# speaker-board.net
KiCad netlist of a schematic drawn in EAGLE
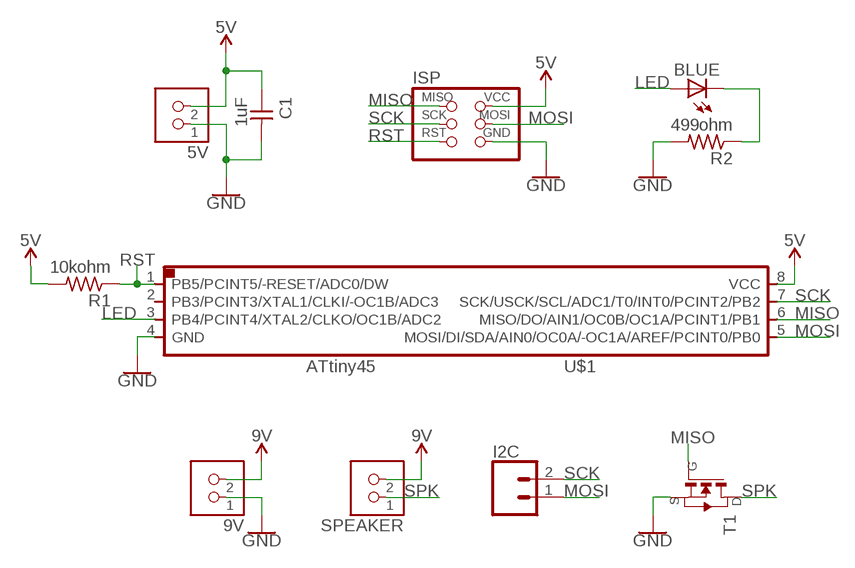
[diagram p0: schematic, sheet 1]

(export (version "E")
  (design (tool "Eeschema 10.0.6"))
  (components
    (comp (ref "5V")
      (value "TERM-1X02-FABLAB")
      (footprint "eagle-import:ED555DS-2DS")
      (libsource (lib "eagle-import") (part "TERM-1X02-FABLAB"))
    )
    (comp (ref "9V")
      (value "TERM-1X02-FABLAB")
      (footprint "eagle-import:ED555DS-2DS")
      (libsource (lib "eagle-import") (part "TERM-1X02-FABLAB"))
    )
    (comp (ref "BLUE")
      (value "LEDFAB1206")
      (footprint "eagle-import:LED1206FAB")
      (libsource (lib "eagle-import") (part "LEDFAB1206"))
    )
    (comp (ref "C1")
      (value "1uF")
      (footprint "eagle-import:C1206FAB")
      (libsource (lib "eagle-import") (part "CAP-UNPOLARIZEDFAB"))
    )
    (comp (ref "I2C")
      (value "CONN_021X02_NO_SILK")
      (footprint "eagle-import:1X02_NO_SILK")
      (libsource (lib "eagle-import") (part "CONN_021X02_NO_SILK"))
    )
    (comp (ref "ISP")
      (value "AVRISPSMD")
      (footprint "eagle-import:2X03SMD")
      (libsource (lib "eagle-import") (part "AVRISPSMD"))
    )
    (comp (ref "R1")
      (value "10kohm")
      (footprint "eagle-import:R1206FAB")
      (libsource (lib "eagle-import") (part "RES-US1206FAB"))
    )
    (comp (ref "R2")
      (value "499ohm")
      (footprint "eagle-import:R1206FAB")
      (libsource (lib "eagle-import") (part "RES-US1206FAB"))
    )
    (comp (ref "SPEAKER")
      (value "TERM-1X02-FABLAB")
      (footprint "eagle-import:ED555DS-2DS")
      (libsource (lib "eagle-import") (part "TERM-1X02-FABLAB"))
    )
    (comp (ref "T1")
      (value "NMOSFETSOT23")
      (footprint "eagle-import:SOT-23")
      (libsource (lib "eagle-import") (part "NMOSFETSOT23"))
    )
    (comp (ref "U$1")
      (value "ATTINY45SI")
      (footprint "eagle-import:SOIC8")
      (libsource (lib "eagle-import") (part "ATTINY45SI"))
    )
  )
  (nets
    (net (code "1") (name "/LED") (class "Default")
      (node (ref "BLUE") (pin "1") (pinfunction "A_1") (pintype "passive"))
      (node (ref "U$1") (pin "3") (pinfunction "PB4/PCINT4/XTAL2/CLKO/OC1B/ADC2_3") (pintype "bidirectional"))
    )
    (net (code "2") (name "/MISO") (class "Default")
      (node (ref "ISP") (pin "1") (pinfunction "MISO_1") (pintype "passive"))
      (node (ref "T1") (pin "3") (pinfunction "G_3") (pintype "passive"))
      (node (ref "U$1") (pin "6") (pinfunction "MISO/DO/AIN1/OC0B/OC1A/PCINT1/PB1_6") (pintype "bidirectional"))
    )
    (net (code "3") (name "/MOSI") (class "Default")
      (node (ref "I2C") (pin "1") (pinfunction "1_1") (pintype "passive"))
      (node (ref "ISP") (pin "4") (pinfunction "MOSI_4") (pintype "passive"))
      (node (ref "U$1") (pin "5") (pinfunction "MOSI/DI/SDA/AIN0/OC0A/-OC1A/AREF/PCINT0/PB0_5") (pintype "bidirectional"))
    )
    (net (code "4") (name "/RST") (class "Default")
      (node (ref "ISP") (pin "5") (pinfunction "RST_5") (pintype "passive"))
      (node (ref "R1") (pin "1") (pinfunction "1_1") (pintype "passive"))
      (node (ref "U$1") (pin "1") (pinfunction "PB5/PCINT5/-RESET/ADC0/DW_1") (pintype "bidirectional"))
    )
    (net (code "5") (name "/SCK") (class "Default")
      (node (ref "I2C") (pin "2") (pinfunction "2_2") (pintype "passive"))
      (node (ref "ISP") (pin "3") (pinfunction "SCK_3") (pintype "passive"))
      (node (ref "U$1") (pin "7") (pinfunction "SCK/USCK/SCL/ADC1/T0/INT0/PCINT2/PB2_7") (pintype "bidirectional"))
    )
    (net (code "6") (name "/SPK") (class "Default")
      (node (ref "SPEAKER") (pin "1") (pinfunction "1_1") (pintype "passive"))
      (node (ref "T1") (pin "1") (pinfunction "D_1") (pintype "passive"))
    )
    (net (code "7") (name "5V") (class "Default")
      (node (ref "5V") (pin "2") (pinfunction "2_2") (pintype "passive"))
      (node (ref "C1") (pin "1") (pinfunction "1_1") (pintype "passive"))
      (node (ref "ISP") (pin "2") (pinfunction "VCC_2") (pintype "passive"))
      (node (ref "R1") (pin "2") (pinfunction "2_2") (pintype "passive"))
      (node (ref "U$1") (pin "8") (pinfunction "VCC_8") (pintype "bidirectional"))
    )
    (net (code "8") (name "9V") (class "Default")
      (node (ref "9V") (pin "2") (pinfunction "2_2") (pintype "passive"))
      (node (ref "SPEAKER") (pin "2") (pinfunction "2_2") (pintype "passive"))
    )
    (net (code "9") (name "GND") (class "Default")
      (node (ref "5V") (pin "1") (pinfunction "1_1") (pintype "passive"))
      (node (ref "9V") (pin "1") (pinfunction "1_1") (pintype "passive"))
      (node (ref "C1") (pin "2") (pinfunction "2_2") (pintype "passive"))
      (node (ref "ISP") (pin "6") (pinfunction "GND_6") (pintype "passive"))
      (node (ref "R2") (pin "2") (pinfunction "2_2") (pintype "passive"))
      (node (ref "T1") (pin "2") (pinfunction "S_2") (pintype "passive"))
      (node (ref "U$1") (pin "4") (pinfunction "GND_4") (pintype "bidirectional"))
    )
    (net (code "10") (name "Net-(BLUE-C)") (class "Default")
      (node (ref "BLUE") (pin "2") (pinfunction "C_2") (pintype "passive"))
      (node (ref "R2") (pin "1") (pinfunction "1_1") (pintype "passive"))
    )
    (net (code "11") (name "unconnected-(U$1-PB3{slash}PCINT3{slash}XTAL1{slash}CLKI{slash}-OC1B{slash}ADC3-Pad2)") (class "Default")
      (node (ref "U$1") (pin "2") (pinfunction "PB3/PCINT3/XTAL1/CLKI/-OC1B/ADC3_2") (pintype "bidirectional"))
    )
  )
)
